# Power_Supply.net
KiCad netlist of a schematic drawn in Altium Designer
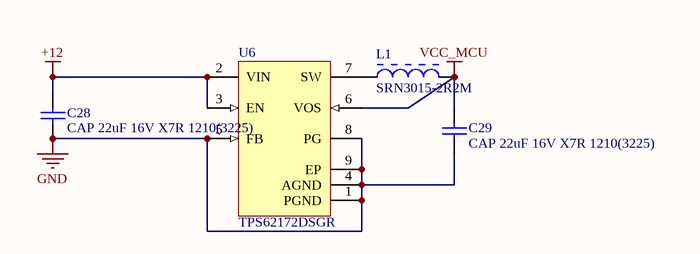
[diagram p0: Power_Supply.SchDoc]

(export (version "E")
  (design (tool "Eeschema 10.0.6"))
  (components
    (comp (ref "C28")
      (value "CAP 22uF 16V X7R 1210(3225)")
      (footprint "CAPC1210(3225)280_L")
      (description "CAP 22uF 16V ±10% 1210 (3225 Metric) Thickness 2.8mm SMD")
      (fields (field (name "TOLERANCE") "Â±10%"))
      (libsource (lib "Altium Content Vault") (part "CAP"))
    )
    (comp (ref "C29")
      (value "CAP 22uF 16V X7R 1210(3225)")
      (footprint "CAPC1210(3225)280_L")
      (description "CAP 22uF 16V ±10% 1210 (3225 Metric) Thickness 2.8mm SMD")
      (fields (field (name "TOLERANCE") "Â±10%"))
      (libsource (lib "Altium Content Vault") (part "CAP"))
    )
    (comp (ref "L1")
      (value "SRN3015-2R2M")
      (footprint "BOUR-SRN3015-2_V")
      (fields (field (name "MANUFACTURER") "Bourns"))
      (libsource (lib "Altium Content Vault") (part "BOUR-IND-2A"))
    )
    (comp (ref "U6")
      (value "TPS62172DSGR")
      (footprint "DSG8-1600X900TP")
      (fields (field (name "MANUFACTURER") "Texas Instruments"))
      (libsource (lib "Texas_Instruments_TPS62172DSGR") (part "TPS62172DSGR"))
    )
  )
  (nets
    (net (code "1") (name "+12") (class "Default")
      (node (ref "C28") (pin "2") (pinfunction "2_2") (pintype "passive"))
      (node (ref "U6") (pin "2") (pinfunction "VIN_2") (pintype "power_in"))
      (node (ref "U6") (pin "3") (pinfunction "EN_3") (pintype "input"))
    )
    (net (code "2") (name "GND") (class "Default")
      (node (ref "C28") (pin "1") (pinfunction "1_1") (pintype "passive"))
      (node (ref "C29") (pin "1") (pinfunction "1_1") (pintype "passive"))
      (node (ref "U6") (pin "1") (pinfunction "PGND_1") (pintype "power_in"))
      (node (ref "U6") (pin "4") (pinfunction "AGND_4") (pintype "power_in"))
      (node (ref "U6") (pin "5") (pinfunction "FB_5") (pintype "input"))
      (node (ref "U6") (pin "8") (pinfunction "PG_8") (pintype "passive"))
      (node (ref "U6") (pin "9") (pinfunction "EP_9") (pintype "power_in"))
    )
    (net (code "3") (name "Net-(U6-SW)") (class "Default")
      (node (ref "L1") (pin "1") (pinfunction "1_1") (pintype "passive"))
      (node (ref "U6") (pin "7") (pinfunction "SW_7") (pintype "power_in"))
    )
    (net (code "4") (name "VCC_MCU") (class "Default")
      (node (ref "C29") (pin "2") (pinfunction "2_2") (pintype "passive"))
      (node (ref "L1") (pin "2") (pinfunction "2_2") (pintype "passive"))
      (node (ref "U6") (pin "6") (pinfunction "VOS_6") (pintype "input"))
    )
  )
)
